# CH32H417MEU6-UHSIF-Top-R0.net
KiCad netlist of a schematic drawn in Altium Designer
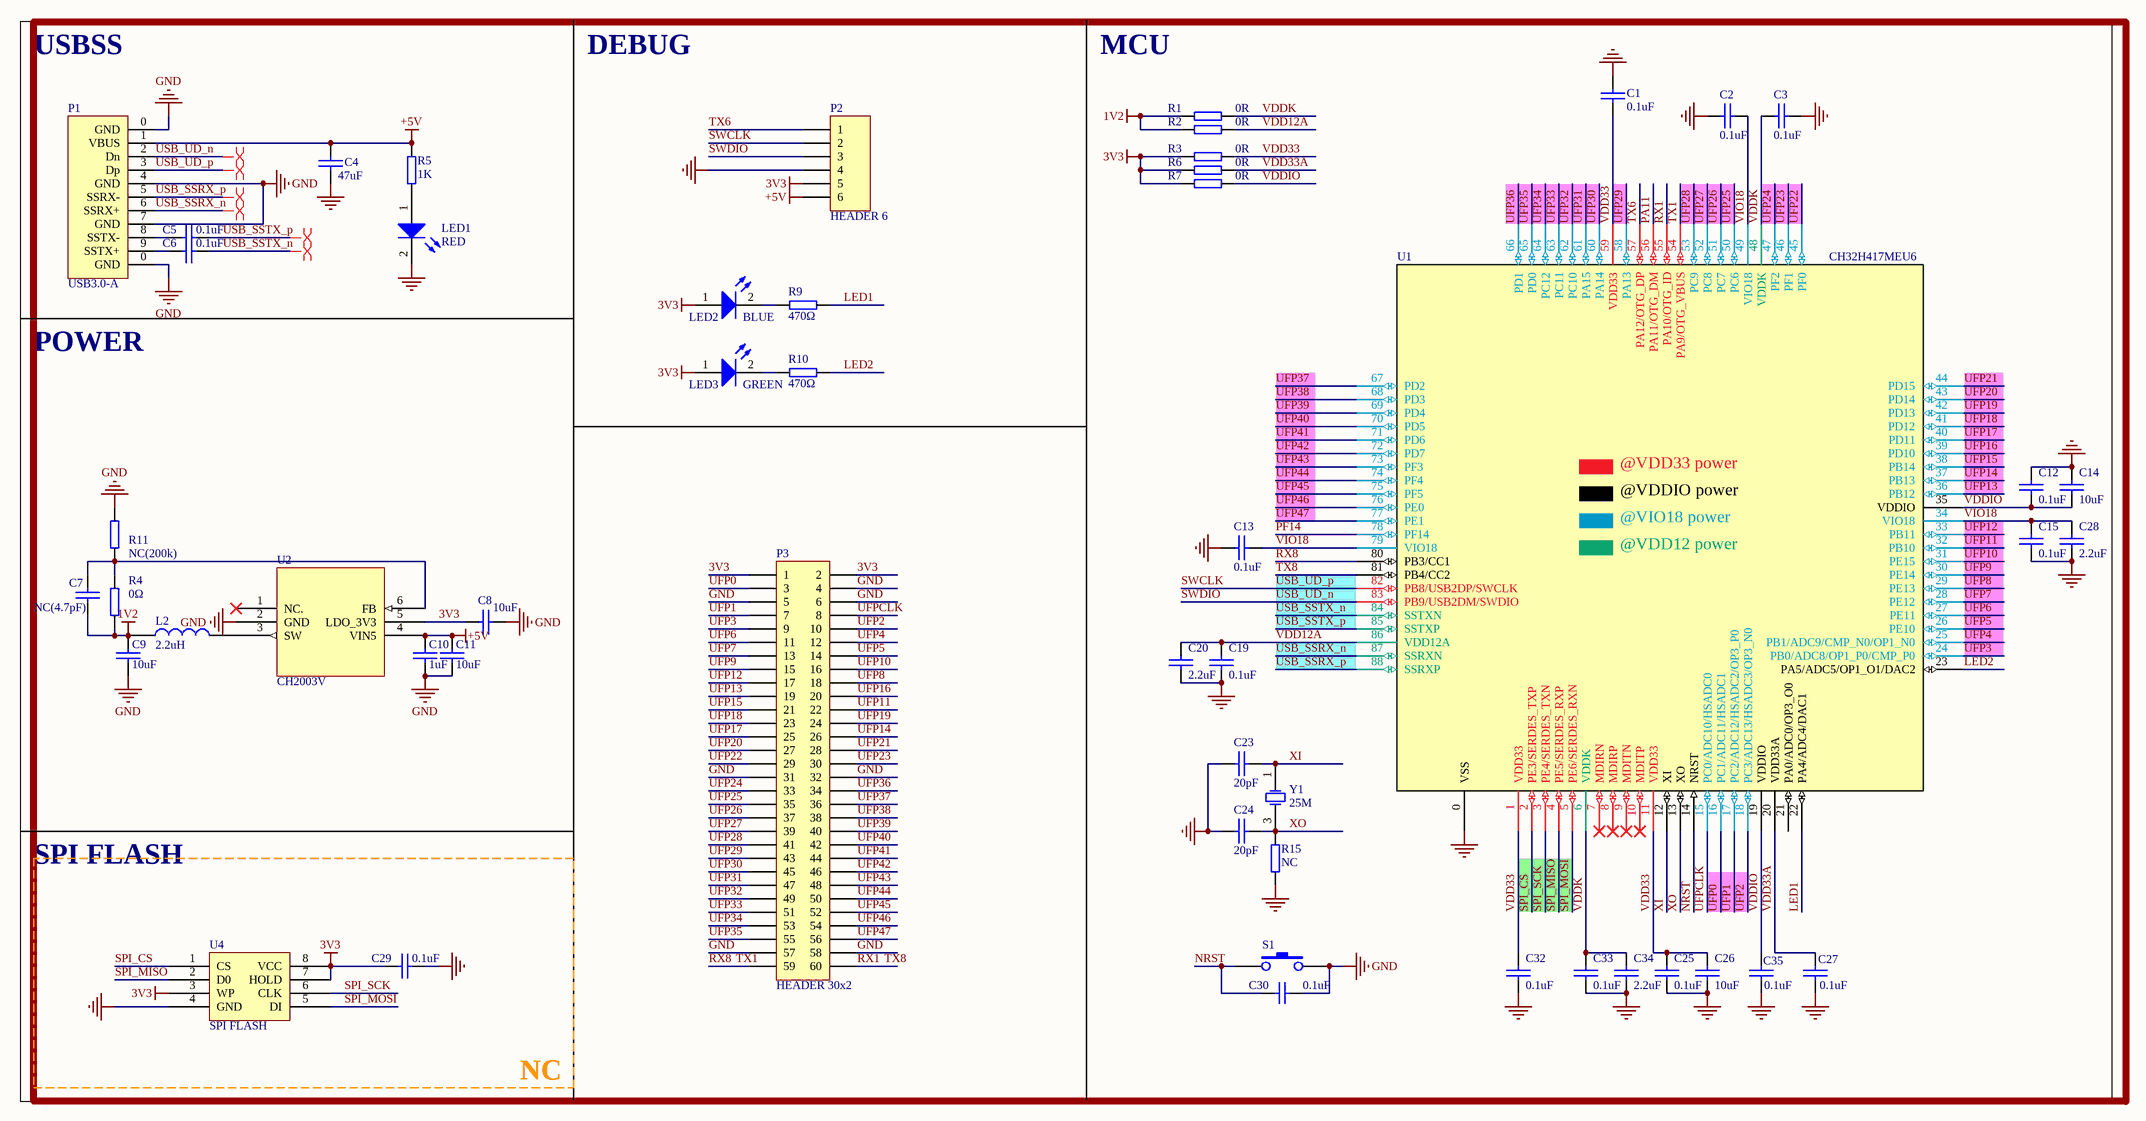
[diagram p0: CH32H417MEU6-UHSIF-Top-R0.SchDoc]

(export (version "E")
  (design (tool "Eeschema 10.0.6"))
  (components
    (comp (ref "C1")
      (value "0.1uF")
      (footprint "0402_C")
      (description "Capacitor")
      (libsource (lib "wch_sch_others") (part "CAP"))
    )
    (comp (ref "C2")
      (value "0.1uF")
      (footprint "0402_C")
      (description "Capacitor")
      (libsource (lib "wch_sch_others") (part "CAP"))
    )
    (comp (ref "C3")
      (value "0.1uF")
      (footprint "0402_C")
      (description "Capacitor")
      (libsource (lib "wch_sch_others") (part "CAP"))
    )
    (comp (ref "C4")
      (value "47uF")
      (footprint "3528_C")
      (description "Capacitor")
      (libsource (lib "wch_sch_others") (part "CAP"))
    )
    (comp (ref "C5")
      (value "0.1uF")
      (footprint "0402_C")
      (description "Capacitor")
      (libsource (lib "wch_sch_others") (part "CAP"))
    )
    (comp (ref "C6")
      (value "0.1uF")
      (footprint "0402_C")
      (description "Capacitor")
      (libsource (lib "wch_sch_others") (part "CAP"))
    )
    (comp (ref "C7")
      (value "NC(4.7pF)")
      (footprint "0402_C")
      (description "Capacitor")
      (libsource (lib "*") (part "CAP"))
    )
    (comp (ref "C8")
      (value "10uF")
      (footprint "0603_C")
      (description "Capacitor")
      (libsource (lib "") (part "CAP_1"))
    )
    (comp (ref "C9")
      (value "10uF")
      (footprint "0603_C")
      (description "Capacitor")
      (libsource (lib "") (part "CAP_1"))
    )
    (comp (ref "C10")
      (value "1uF")
      (footprint "0402_C")
      (description "Capacitor")
      (libsource (lib "*") (part "CAP"))
    )
    (comp (ref "C11")
      (value "10uF")
      (footprint "0603_C")
      (description "Capacitor")
      (libsource (lib "") (part "CAP_1"))
    )
    (comp (ref "C12")
      (value "0.1uF")
      (footprint "0402_C")
      (description "Capacitor")
      (libsource (lib "wch_sch_others") (part "CAP"))
    )
    (comp (ref "C13")
      (value "0.1uF")
      (footprint "0402_C")
      (description "Capacitor")
      (libsource (lib "wch_sch_others") (part "CAP"))
    )
    (comp (ref "C14")
      (value "10uF")
      (footprint "0402_C")
      (description "Capacitor")
      (libsource (lib "wch_sch_others") (part "CAP"))
    )
    (comp (ref "C15")
      (value "0.1uF")
      (footprint "0402_C")
      (description "Capacitor")
      (libsource (lib "wch_sch_others") (part "CAP"))
    )
    (comp (ref "C19")
      (value "0.1uF")
      (footprint "0402_C")
      (description "Capacitor")
      (libsource (lib "wch_sch_others") (part "CAP"))
    )
    (comp (ref "C20")
      (value "2.2uF")
      (footprint "0402_C")
      (description "Capacitor")
      (libsource (lib "wch_sch_others") (part "CAP"))
    )
    (comp (ref "C23")
      (value "20pF")
      (footprint "0402_C")
      (description "Capacitor")
      (libsource (lib "wch_sch_others") (part "CAP"))
    )
    (comp (ref "C24")
      (value "20pF")
      (footprint "0402_C")
      (description "Capacitor")
      (libsource (lib "wch_sch_others") (part "CAP"))
    )
    (comp (ref "C25")
      (value "0.1uF")
      (footprint "0402_C")
      (description "Capacitor")
      (libsource (lib "wch_sch_others") (part "CAP"))
    )
    (comp (ref "C26")
      (value "10uF")
      (footprint "0402_C")
      (description "Capacitor")
      (libsource (lib "wch_sch_others") (part "CAP"))
    )
    (comp (ref "C27")
      (value "0.1uF")
      (footprint "0402_C")
      (description "Capacitor")
      (libsource (lib "wch_sch_others") (part "CAP"))
    )
    (comp (ref "C28")
      (value "2.2uF")
      (footprint "0402_C")
      (description "Capacitor")
      (libsource (lib "wch_sch_others") (part "CAP"))
    )
    (comp (ref "C29")
      (value "0.1uF")
      (footprint "0402_C")
      (description "Capacitor")
      (libsource (lib "wch_sch_others") (part "CAP"))
    )
    (comp (ref "C30")
      (value "0.1uF")
      (footprint "0402_C")
      (description "Capacitor")
      (libsource (lib "Miscellaneous Devices") (part "Cap"))
    )
    (comp (ref "C32")
      (value "0.1uF")
      (footprint "0402_C")
      (description "Capacitor")
      (libsource (lib "wch_sch_others") (part "CAP"))
    )
    (comp (ref "C33")
      (value "0.1uF")
      (footprint "0402_C")
      (description "Capacitor")
      (libsource (lib "wch_sch_others") (part "CAP"))
    )
    (comp (ref "C34")
      (value "2.2uF")
      (footprint "0402_C")
      (description "Capacitor")
      (libsource (lib "wch_sch_others") (part "CAP"))
    )
    (comp (ref "C35")
      (value "0.1uF")
      (footprint "0402_C")
      (description "Capacitor")
      (libsource (lib "wch_sch_others") (part "CAP"))
    )
    (comp (ref "L2") (value "2.2uH") (footprint "CD32") (libsource (lib "*") (part "INDUCTOR")))
    (comp (ref "LED1")
      (value "RED")
      (footprint "MYPCB:0603+")
      (description "Typical INFRARED GaAs LED")
      (libsource (lib "wch_sch_others") (part "LED"))
    )
    (comp (ref "LED2")
      (value "BLUE")
      (footprint "MYPCB:0603+")
      (description "Typical INFRARED GaAs LED")
      (libsource (lib "wch_sch_others") (part "LED"))
    )
    (comp (ref "LED3")
      (value "GREEN")
      (footprint "MYPCB:0603+")
      (description "Typical INFRARED GaAs LED")
      (libsource (lib "wch_sch_others") (part "LED"))
    )
    (comp (ref "P1")
      (value "USB3.0-A")
      (footprint "USB3.0-A-Receptacle")
      (libsource (lib "wch_sch_others") (part "USB3.0-A"))
    )
    (comp (ref "P2")
      (value "HEADER 6")
      (footprint "SIP6-2.54mm")
      (description "Header, 6-Pin")
      (libsource (lib "wch_sch_others") (part "HEADER 6"))
    )
    (comp (ref "P3")
      (value "HEADER 30x2")
      (footprint "MYPCB:BTB-60P-P0.5-FR")
      (description "Header, 30-Pin, Dual row")
      (libsource (lib "wch_sch_others") (part "HEADER 30x2"))
    )
    (comp (ref "R1") (value "0R") (footprint "0603") (libsource (lib "wch_sch_others") (part "RES")))
    (comp (ref "R2") (value "0R") (footprint "0603") (libsource (lib "wch_sch_others") (part "RES")))
    (comp (ref "R3") (value "0R") (footprint "0603") (libsource (lib "wch_sch_others") (part "RES")))
    (comp (ref "R4") (value "0Ω") (footprint "0402") (libsource (lib "wch_sch_others") (part "RES")))
    (comp (ref "R5") (value "1K") (footprint "0402") (libsource (lib "wch_sch_others") (part "RES")))
    (comp (ref "R6") (value "0R") (footprint "0603") (libsource (lib "wch_sch_others") (part "RES")))
    (comp (ref "R7") (value "0R") (footprint "0603") (libsource (lib "wch_sch_others") (part "RES")))
    (comp (ref "R9") (value "470Ω") (footprint "0402") (libsource (lib "wch_sch_others") (part "RES")))
    (comp (ref "R10") (value "470Ω") (footprint "0402") (libsource (lib "wch_sch_others") (part "RES")))
    (comp (ref "R11") (value "NC(200k)") (footprint "0402") (libsource (lib "wch_sch_others") (part "RES")))
    (comp (ref "R15") (value "NC") (footprint "0402") (libsource (lib "*") (part "RES")))
    (comp (ref "S1") (value "~") (footprint "贴片按键") (libsource (lib "wch_sch_others") (part "KEY1")))
    (comp (ref "U1")
      (value "CH32H417MEU6")
      (footprint "QFN88_10X10")
      (description "RISC-V FPU HD-MCU, 384MHz, USB3.0 & PD, 100M Ethernet, DVP, SDMMC, QSPI, OPA, ADC, DAC")
      (libsource (lib "DHXXXSCH") (part "CH32H417MEU6"))
    )
    (comp (ref "U2")
      (value "CH2003V")
      (footprint "SOT-23-6")
      (description "Step-Down DC-DC Converter, 5V input, FB 0.6V, 800mA output, with LDO 3.3V * 200mA")
      (libsource (lib "DHXXXSCH") (part "CH2003K"))
    )
    (comp (ref "U4")
      (value "SPI FLASH")
      (footprint "SOIC-8_208mil")
      (libsource (lib "wch_sch_others") (part "W25Q64"))
    )
    (comp (ref "Y1")
      (value "25M")
      (footprint "XT3225")
      (description "Crystal Oscillator")
      (fields (field (name "PUBLISHER") "Altium Limited"))
      (libsource (lib "Miscellaneous Devices") (part "XTAL"))
    )
  )
  (nets
    (net (code "1") (name "+5V") (class "Default")
      (node (ref "C10") (pin "2") (pinfunction "2_2") (pintype "passive"))
      (node (ref "C11") (pin "2") (pinfunction "2_2") (pintype "passive"))
      (node (ref "C4") (pin "1") (pinfunction "1_1") (pintype "passive"))
      (node (ref "P1") (pin "1") (pinfunction "VBUS_1") (pintype "passive"))
      (node (ref "P2") (pin "6") (pinfunction "6_6") (pintype "passive"))
      (node (ref "R5") (pin "2") (pintype "passive"))
      (node (ref "U2") (pin "4") (pinfunction "VIN5_4") (pintype "power_in"))
    )
    (net (code "2") (name "/LED1") (class "Default")
      (node (ref "R9") (pin "1") (pintype "passive"))
      (node (ref "U1") (pin "22") (pinfunction "PA4/ADC4/DAC1_22") (pintype "bidirectional"))
    )
    (net (code "3") (name "/LED2") (class "Default")
      (node (ref "R10") (pin "1") (pintype "passive"))
      (node (ref "U1") (pin "23") (pinfunction "PA5/ADC5/OP1_O1/DAC2_23") (pintype "bidirectional"))
    )
    (net (code "4") (name "/NRST") (class "Default")
      (node (ref "C30") (pin "2") (pinfunction "2_2") (pintype "passive"))
      (node (ref "S1") (pin "1") (pinfunction "1_1") (pintype "passive"))
      (node (ref "U1") (pin "14") (pinfunction "NRST_14") (pintype "input"))
    )
    (net (code "5") (name "/PA11") (class "Default")
      (node (ref "U1") (pin "56") (pinfunction "PA11/OTG_DM_56") (pintype "bidirectional"))
    )
    (net (code "6") (name "/PF14") (class "Default")
      (node (ref "U1") (pin "78") (pinfunction "PF14_78") (pintype "bidirectional"))
    )
    (net (code "7") (name "/RX1") (class "Default")
      (node (ref "P3") (pin "60") (pinfunction "60_60") (pintype "passive"))
      (node (ref "U1") (pin "55") (pinfunction "PA10/OTG_ID_55") (pintype "bidirectional"))
      (node (ref "U1") (pin "81") (pinfunction "PB4/CC2_81") (pintype "bidirectional"))
    )
    (net (code "8") (name "/RX8") (class "Default")
      (node (ref "P3") (pin "59") (pinfunction "59_59") (pintype "passive"))
      (node (ref "U1") (pin "54") (pinfunction "PA9/OTG_VBUS_54") (pintype "bidirectional"))
      (node (ref "U1") (pin "80") (pinfunction "PB3/CC1_80") (pintype "bidirectional"))
    )
    (net (code "9") (name "/SPI_CS") (class "Default")
      (node (ref "U1") (pin "2") (pinfunction "PE3/SERDES_TXP_2") (pintype "bidirectional"))
      (node (ref "U4") (pin "1") (pinfunction "CS_1") (pintype "passive"))
    )
    (net (code "10") (name "/SPI_MISO") (class "Default")
      (node (ref "U1") (pin "4") (pinfunction "PE5/SERDES_RXP_4") (pintype "bidirectional"))
      (node (ref "U4") (pin "2") (pinfunction "D0_2") (pintype "passive"))
    )
    (net (code "11") (name "/SPI_MOSI") (class "Default")
      (node (ref "U1") (pin "5") (pinfunction "PE6/SERDES_RXN_5") (pintype "bidirectional"))
      (node (ref "U4") (pin "5") (pinfunction "DI_5") (pintype "passive"))
    )
    (net (code "12") (name "/SPI_SCK") (class "Default")
      (node (ref "U1") (pin "3") (pinfunction "PE4/SERDES_TXN_3") (pintype "bidirectional"))
      (node (ref "U4") (pin "6") (pinfunction "CLK_6") (pintype "passive"))
    )
    (net (code "13") (name "/SWCLK") (class "Default")
      (node (ref "P1") (pin "3") (pinfunction "Dp_3") (pintype "passive"))
      (node (ref "P2") (pin "2") (pinfunction "2_2") (pintype "passive"))
      (node (ref "U1") (pin "82") (pinfunction "PB8/USB2DP/SWCLK_82") (pintype "bidirectional"))
    )
    (net (code "14") (name "/SWDIO") (class "Default")
      (node (ref "P1") (pin "2") (pinfunction "Dn_2") (pintype "passive"))
      (node (ref "P2") (pin "3") (pinfunction "3_3") (pintype "passive"))
      (node (ref "U1") (pin "83") (pinfunction "PB9/USB2DM/SWDIO_83") (pintype "bidirectional"))
    )
    (net (code "15") (name "/TX6") (class "Default")
      (node (ref "P2") (pin "1") (pinfunction "1_1") (pintype "passive"))
      (node (ref "U1") (pin "57") (pinfunction "PA12/OTG_DP_57") (pintype "bidirectional"))
    )
    (net (code "16") (name "/UFP0") (class "Default")
      (node (ref "P3") (pin "3") (pinfunction "3_3") (pintype "passive"))
      (node (ref "U1") (pin "16") (pinfunction "PC1/ADC11/HSADC1_16") (pintype "bidirectional"))
    )
    (net (code "17") (name "/UFP1") (class "Default")
      (node (ref "P3") (pin "7") (pinfunction "7_7") (pintype "passive"))
      (node (ref "U1") (pin "17") (pinfunction "PC2/ADC12/HSADC2/OP3_P0_17") (pintype "bidirectional"))
    )
    (net (code "18") (name "/UFP2") (class "Default")
      (node (ref "P3") (pin "10") (pinfunction "10_10") (pintype "passive"))
      (node (ref "U1") (pin "18") (pinfunction "PC3/ADC13/HSADC3/OP3_N0_18") (pintype "bidirectional"))
    )
    (net (code "19") (name "/UFP3") (class "Default")
      (node (ref "P3") (pin "9") (pinfunction "9_9") (pintype "passive"))
      (node (ref "U1") (pin "24") (pinfunction "PB0/ADC8/OP1_P0/CMP_P0_24") (pintype "bidirectional"))
    )
    (net (code "20") (name "/UFP4") (class "Default")
      (node (ref "P3") (pin "12") (pinfunction "12_12") (pintype "passive"))
      (node (ref "U1") (pin "25") (pinfunction "PB1/ADC9/CMP_N0/OP1_N0_25") (pintype "bidirectional"))
    )
    (net (code "21") (name "/UFP5") (class "Default")
      (node (ref "P3") (pin "14") (pinfunction "14_14") (pintype "passive"))
      (node (ref "U1") (pin "26") (pinfunction "PE10_26") (pintype "bidirectional"))
    )
    (net (code "22") (name "/UFP6") (class "Default")
      (node (ref "P3") (pin "11") (pinfunction "11_11") (pintype "passive"))
      (node (ref "U1") (pin "27") (pinfunction "PE11_27") (pintype "bidirectional"))
    )
    (net (code "23") (name "/UFP7") (class "Default")
      (node (ref "P3") (pin "13") (pinfunction "13_13") (pintype "passive"))
      (node (ref "U1") (pin "28") (pinfunction "PE12_28") (pintype "bidirectional"))
    )
    (net (code "24") (name "/UFP8") (class "Default")
      (node (ref "P3") (pin "18") (pinfunction "18_18") (pintype "passive"))
      (node (ref "U1") (pin "29") (pinfunction "PE13_29") (pintype "bidirectional"))
    )
    (net (code "25") (name "/UFP9") (class "Default")
      (node (ref "P3") (pin "15") (pinfunction "15_15") (pintype "passive"))
      (node (ref "U1") (pin "30") (pinfunction "PE14_30") (pintype "bidirectional"))
    )
    (net (code "26") (name "/UFP10") (class "Default")
      (node (ref "P3") (pin "16") (pinfunction "16_16") (pintype "passive"))
      (node (ref "U1") (pin "31") (pinfunction "PE15_31") (pintype "bidirectional"))
    )
    (net (code "27") (name "/UFP11") (class "Default")
      (node (ref "P3") (pin "22") (pinfunction "22_22") (pintype "passive"))
      (node (ref "U1") (pin "32") (pinfunction "PB10_32") (pintype "bidirectional"))
    )
    (net (code "28") (name "/UFP12") (class "Default")
      (node (ref "P3") (pin "17") (pinfunction "17_17") (pintype "passive"))
      (node (ref "U1") (pin "33") (pinfunction "PB11_33") (pintype "bidirectional"))
    )
    (net (code "29") (name "/UFP13") (class "Default")
      (node (ref "P3") (pin "19") (pinfunction "19_19") (pintype "passive"))
      (node (ref "U1") (pin "36") (pinfunction "PB12_36") (pintype "bidirectional"))
    )
    (net (code "30") (name "/UFP14") (class "Default")
      (node (ref "P3") (pin "26") (pinfunction "26_26") (pintype "passive"))
      (node (ref "U1") (pin "37") (pinfunction "PB13_37") (pintype "bidirectional"))
    )
    (net (code "31") (name "/UFP15") (class "Default")
      (node (ref "P3") (pin "21") (pinfunction "21_21") (pintype "passive"))
      (node (ref "U1") (pin "38") (pinfunction "PB14_38") (pintype "bidirectional"))
    )
    (net (code "32") (name "/UFP16") (class "Default")
      (node (ref "P3") (pin "20") (pinfunction "20_20") (pintype "passive"))
      (node (ref "U1") (pin "39") (pinfunction "PD10_39") (pintype "bidirectional"))
    )
    (net (code "33") (name "/UFP17") (class "Default")
      (node (ref "P3") (pin "25") (pinfunction "25_25") (pintype "passive"))
      (node (ref "U1") (pin "40") (pinfunction "PD11_40") (pintype "bidirectional"))
    )
    (net (code "34") (name "/UFP18") (class "Default")
      (node (ref "P3") (pin "23") (pinfunction "23_23") (pintype "passive"))
      (node (ref "U1") (pin "41") (pinfunction "PD12_41") (pintype "bidirectional"))
    )
    (net (code "35") (name "/UFP19") (class "Default")
      (node (ref "P3") (pin "24") (pinfunction "24_24") (pintype "passive"))
      (node (ref "U1") (pin "42") (pinfunction "PD13_42") (pintype "bidirectional"))
    )
    (net (code "36") (name "/UFP20") (class "Default")
      (node (ref "P3") (pin "27") (pinfunction "27_27") (pintype "passive"))
      (node (ref "U1") (pin "43") (pinfunction "PD14_43") (pintype "bidirectional"))
    )
    (net (code "37") (name "/UFP21") (class "Default")
      (node (ref "P3") (pin "28") (pinfunction "28_28") (pintype "passive"))
      (node (ref "U1") (pin "44") (pinfunction "PD15_44") (pintype "bidirectional"))
    )
    (net (code "38") (name "/UFP22") (class "Default")
      (node (ref "P3") (pin "29") (pinfunction "29_29") (pintype "passive"))
      (node (ref "U1") (pin "45") (pinfunction "PF0_45") (pintype "bidirectional"))
    )
    (net (code "39") (name "/UFP23") (class "Default")
      (node (ref "P3") (pin "30") (pinfunction "30_30") (pintype "passive"))
      (node (ref "U1") (pin "46") (pinfunction "PF1_46") (pintype "bidirectional"))
    )
    (net (code "40") (name "/UFP24") (class "Default")
      (node (ref "P3") (pin "33") (pinfunction "33_33") (pintype "passive"))
      (node (ref "U1") (pin "47") (pinfunction "PF2_47") (pintype "bidirectional"))
    )
    (net (code "41") (name "/UFP25") (class "Default")
      (node (ref "P3") (pin "35") (pinfunction "35_35") (pintype "passive"))
      (node (ref "U1") (pin "50") (pinfunction "PC6_50") (pintype "bidirectional"))
    )
    (net (code "42") (name "/UFP26") (class "Default")
      (node (ref "P3") (pin "37") (pinfunction "37_37") (pintype "passive"))
      (node (ref "U1") (pin "51") (pinfunction "PC7_51") (pintype "bidirectional"))
    )
    (net (code "43") (name "/UFP27") (class "Default")
      (node (ref "P3") (pin "39") (pinfunction "39_39") (pintype "passive"))
      (node (ref "U1") (pin "52") (pinfunction "PC8_52") (pintype "bidirectional"))
    )
    (net (code "44") (name "/UFP28") (class "Default")
      (node (ref "P3") (pin "41") (pinfunction "41_41") (pintype "passive"))
      (node (ref "U1") (pin "53") (pinfunction "PC9_53") (pintype "bidirectional"))
    )
    (net (code "45") (name "/UFP29") (class "Default")
      (node (ref "P3") (pin "43") (pinfunction "43_43") (pintype "passive"))
      (node (ref "U1") (pin "58") (pinfunction "PA13_58") (pintype "bidirectional"))
    )
    (net (code "46") (name "/UFP30") (class "Default")
      (node (ref "P3") (pin "45") (pinfunction "45_45") (pintype "passive"))
      (node (ref "U1") (pin "60") (pinfunction "PA14_60") (pintype "bidirectional"))
    )
    (net (code "47") (name "/UFP31") (class "Default")
      (node (ref "P3") (pin "47") (pinfunction "47_47") (pintype "passive"))
      (node (ref "U1") (pin "61") (pinfunction "PA15_61") (pintype "bidirectional"))
    )
    (net (code "48") (name "/UFP32") (class "Default")
      (node (ref "P3") (pin "49") (pinfunction "49_49") (pintype "passive"))
      (node (ref "U1") (pin "62") (pinfunction "PC10_62") (pintype "bidirectional"))
    )
    (net (code "49") (name "/UFP33") (class "Default")
      (node (ref "P3") (pin "51") (pinfunction "51_51") (pintype "passive"))
      (node (ref "U1") (pin "63") (pinfunction "PC11_63") (pintype "bidirectional"))
    )
    (net (code "50") (name "/UFP34") (class "Default")
      (node (ref "P3") (pin "53") (pinfunction "53_53") (pintype "passive"))
      (node (ref "U1") (pin "64") (pinfunction "PC12_64") (pintype "bidirectional"))
    )
    (net (code "51") (name "/UFP35") (class "Default")
      (node (ref "P3") (pin "55") (pinfunction "55_55") (pintype "passive"))
      (node (ref "U1") (pin "65") (pinfunction "PD0_65") (pintype "bidirectional"))
    )
    (net (code "52") (name "/UFP36") (class "Default")
      (node (ref "P3") (pin "34") (pinfunction "34_34") (pintype "passive"))
      (node (ref "U1") (pin "66") (pinfunction "PD1_66") (pintype "bidirectional"))
    )
    (net (code "53") (name "/UFP37") (class "Default")
      (node (ref "P3") (pin "36") (pinfunction "36_36") (pintype "passive"))
      (node (ref "U1") (pin "67") (pinfunction "PD2_67") (pintype "bidirectional"))
    )
    (net (code "54") (name "/UFP38") (class "Default")
      (node (ref "P3") (pin "38") (pinfunction "38_38") (pintype "passive"))
      (node (ref "U1") (pin "68") (pinfunction "PD3_68") (pintype "bidirectional"))
    )
    (net (code "55") (name "/UFP39") (class "Default")
      (node (ref "P3") (pin "40") (pinfunction "40_40") (pintype "passive"))
      (node (ref "U1") (pin "69") (pinfunction "PD4_69") (pintype "bidirectional"))
    )
    (net (code "56") (name "/UFP40") (class "Default")
      (node (ref "P3") (pin "42") (pinfunction "42_42") (pintype "passive"))
      (node (ref "U1") (pin "70") (pinfunction "PD5_70") (pintype "bidirectional"))
    )
    (net (code "57") (name "/UFP41") (class "Default")
      (node (ref "P3") (pin "44") (pinfunction "44_44") (pintype "passive"))
      (node (ref "U1") (pin "71") (pinfunction "PD6_71") (pintype "bidirectional"))
    )
    (net (code "58") (name "/UFP42") (class "Default")
      (node (ref "P3") (pin "46") (pinfunction "46_46") (pintype "passive"))
      (node (ref "U1") (pin "72") (pinfunction "PD7_72") (pintype "bidirectional"))
    )
    (net (code "59") (name "/UFP43") (class "Default")
      (node (ref "P3") (pin "48") (pinfunction "48_48") (pintype "passive"))
      (node (ref "U1") (pin "73") (pinfunction "PF3_73") (pintype "bidirectional"))
    )
    (net (code "60") (name "/UFP44") (class "Default")
      (node (ref "P3") (pin "50") (pinfunction "50_50") (pintype "passive"))
      (node (ref "U1") (pin "74") (pinfunction "PF4_74") (pintype "bidirectional"))
    )
    (net (code "61") (name "/UFP45") (class "Default")
      (node (ref "P3") (pin "52") (pinfunction "52_52") (pintype "passive"))
      (node (ref "U1") (pin "75") (pinfunction "PF5_75") (pintype "bidirectional"))
    )
    (net (code "62") (name "/UFP46") (class "Default")
      (node (ref "P3") (pin "54") (pinfunction "54_54") (pintype "passive"))
      (node (ref "U1") (pin "76") (pinfunction "PE0_76") (pintype "bidirectional"))
    )
    (net (code "63") (name "/UFP47") (class "Default")
      (node (ref "P3") (pin "56") (pinfunction "56_56") (pintype "passive"))
      (node (ref "U1") (pin "77") (pinfunction "PE1_77") (pintype "bidirectional"))
    )
    (net (code "64") (name "/UFPCLK") (class "Default")
      (node (ref "P3") (pin "8") (pinfunction "8_8") (pintype "passive"))
      (node (ref "U1") (pin "15") (pinfunction "PC0/ADC10/HSADC0_15") (pintype "bidirectional"))
    )
    (net (code "65") (name "/USB_SSRX_n") (class "Default")
      (node (ref "P1") (pin "6") (pinfunction "SSRX+_6") (pintype "passive"))
      (node (ref "U1") (pin "87") (pinfunction "SSRXN_87") (pintype "bidirectional"))
    )
    (net (code "66") (name "/USB_SSRX_p") (class "Default")
      (node (ref "P1") (pin "5") (pinfunction "SSRX-_5") (pintype "passive"))
      (node (ref "U1") (pin "88") (pinfunction "SSRXP_88") (pintype "bidirectional"))
    )
    (net (code "67") (name "/USB_SSTX_n") (class "Default")
      (node (ref "C6") (pin "1") (pinfunction "1_1") (pintype "passive"))
      (node (ref "U1") (pin "84") (pinfunction "SSTXN_84") (pintype "bidirectional"))
    )
    (net (code "68") (name "/USB_SSTX_p") (class "Default")
      (node (ref "C5") (pin "1") (pinfunction "1_1") (pintype "passive"))
      (node (ref "U1") (pin "85") (pinfunction "SSTXP_85") (pintype "bidirectional"))
    )
    (net (code "69") (name "/VDD12A") (class "Default")
      (node (ref "C19") (pin "2") (pinfunction "2_2") (pintype "passive"))
      (node (ref "C20") (pin "2") (pinfunction "2_2") (pintype "passive"))
      (node (ref "R2") (pin "1") (pintype "passive"))
      (node (ref "U1") (pin "86") (pinfunction "VDD12A_86") (pintype "power_in"))
    )
    (net (code "70") (name "/VDD33") (class "Default")
      (node (ref "C1") (pin "1") (pinfunction "1_1") (pintype "passive"))
      (node (ref "C25") (pin "2") (pinfunction "2_2") (pintype "passive"))
      (node (ref "C26") (pin "2") (pinfunction "2_2") (pintype "passive"))
      (node (ref "C32") (pin "2") (pinfunction "2_2") (pintype "passive"))
      (node (ref "R3") (pin "1") (pintype "passive"))
      (node (ref "U1") (pin "1") (pinfunction "VDD33_1") (pintype "power_in"))
      (node (ref "U1") (pin "11") (pinfunction "VDD33_11") (pintype "power_in"))
      (node (ref "U1") (pin "59") (pinfunction "VDD33_59") (pintype "power_in"))
    )
    (net (code "71") (name "/VDD33A") (class "Default")
      (node (ref "C27") (pin "2") (pinfunction "2_2") (pintype "passive"))
      (node (ref "R6") (pin "1") (pintype "passive"))
      (node (ref "U1") (pin "20") (pinfunction "VDD33A_20") (pintype "power_in"))
    )
    (net (code "72") (name "/VDDIO") (class "Default")
      (node (ref "C12") (pin "1") (pinfunction "1_1") (pintype "passive"))
      (node (ref "C14") (pin "1") (pinfunction "1_1") (pintype "passive"))
      (node (ref "C35") (pin "2") (pinfunction "2_2") (pintype "passive"))
      (node (ref "R7") (pin "1") (pintype "passive"))
      (node (ref "U1") (pin "19") (pinfunction "VDDIO_19") (pintype "power_in"))
      (node (ref "U1") (pin "35") (pinfunction "VDDIO_35") (pintype "power_in"))
    )
    (net (code "73") (name "/VDDK") (class "Default")
      (node (ref "C3") (pin "2") (pinfunction "2_2") (pintype "passive"))
      (node (ref "C33") (pin "2") (pinfunction "2_2") (pintype "passive"))
      (node (ref "C34") (pin "2") (pinfunction "2_2") (pintype "passive"))
      (node (ref "R1") (pin "1") (pintype "passive"))
      (node (ref "U1") (pin "48") (pinfunction "VDDK_48") (pintype "power_in"))
      (node (ref "U1") (pin "6") (pinfunction "VDDK_6") (pintype "power_in"))
    )
    (net (code "74") (name "/VIO18") (class "Default")
      (node (ref "C13") (pin "1") (pinfunction "1_1") (pintype "passive"))
      (node (ref "C15") (pin "2") (pinfunction "2_2") (pintype "passive"))
      (node (ref "C2") (pin "1") (pinfunction "1_1") (pintype "passive"))
      (node (ref "C28") (pin "2") (pinfunction "2_2") (pintype "passive"))
      (node (ref "U1") (pin "34") (pinfunction "VIO18_34") (pintype "power_in"))
      (node (ref "U1") (pin "49") (pinfunction "VIO18_49") (pintype "power_in"))
      (node (ref "U1") (pin "79") (pinfunction "VIO18_79") (pintype "power_in"))
    )
    (net (code "75") (name "/XI") (class "Default")
      (node (ref "C23") (pin "2") (pinfunction "2_2") (pintype "passive"))
      (node (ref "U1") (pin "12") (pinfunction "XI_12") (pintype "bidirectional"))
      (node (ref "Y1") (pin "1") (pinfunction "OSC1_1") (pintype "passive"))
    )
    (net (code "76") (name "/XO") (class "Default")
      (node (ref "C24") (pin "2") (pinfunction "2_2") (pintype "passive"))
      (node (ref "R15") (pin "2") (pintype "passive"))
      (node (ref "U1") (pin "13") (pinfunction "XO_13") (pintype "bidirectional"))
      (node (ref "Y1") (pin "3") (pinfunction "OSC2_3") (pintype "passive"))
    )
    (net (code "77") (name "1V2") (class "Default")
      (node (ref "C7") (pin "1") (pinfunction "1_1") (pintype "passive"))
      (node (ref "C9") (pin "2") (pinfunction "2_2") (pintype "passive"))
      (node (ref "L2") (pin "2") (pinfunction "2_2") (pintype "passive"))
      (node (ref "R1") (pin "2") (pintype "passive"))
      (node (ref "R2") (pin "2") (pintype "passive"))
      (node (ref "R4") (pin "1") (pintype "passive"))
    )
    (net (code "78") (name "3V3") (class "Default")
      (node (ref "C29") (pin "2") (pinfunction "2_2") (pintype "passive"))
      (node (ref "C8") (pin "2") (pinfunction "2_2") (pintype "passive"))
      (node (ref "LED2") (pin "1") (pinfunction "A_1") (pintype "passive"))
      (node (ref "LED3") (pin "1") (pinfunction "A_1") (pintype "passive"))
      (node (ref "P2") (pin "5") (pinfunction "5_5") (pintype "passive"))
      (node (ref "P3") (pin "1") (pinfunction "1_1") (pintype "passive"))
      (node (ref "P3") (pin "2") (pinfunction "2_2") (pintype "passive"))
      (node (ref "R3") (pin "2") (pintype "passive"))
      (node (ref "R6") (pin "2") (pintype "passive"))
      (node (ref "R7") (pin "2") (pintype "passive"))
      (node (ref "U2") (pin "5") (pinfunction "LDO_3V3_5") (pintype "power_in"))
      (node (ref "U4") (pin "3") (pinfunction "WP_3") (pintype "passive"))
      (node (ref "U4") (pin "7") (pinfunction "HOLD_7") (pintype "passive"))
      (node (ref "U4") (pin "8") (pinfunction "VCC_8") (pintype "passive"))
    )
    (net (code "79") (name "GND") (class "Default")
      (node (ref "C1") (pin "2") (pinfunction "2_2") (pintype "passive"))
      (node (ref "C10") (pin "1") (pinfunction "1_1") (pintype "passive"))
      (node (ref "C11") (pin "1") (pinfunction "1_1") (pintype "passive"))
      (node (ref "C12") (pin "2") (pinfunction "2_2") (pintype "passive"))
      (node (ref "C13") (pin "2") (pinfunction "2_2") (pintype "passive"))
      (node (ref "C14") (pin "2") (pinfunction "2_2") (pintype "passive"))
      (node (ref "C15") (pin "1") (pinfunction "1_1") (pintype "passive"))
      (node (ref "C19") (pin "1") (pinfunction "1_1") (pintype "passive"))
      (node (ref "C2") (pin "2") (pinfunction "2_2") (pintype "passive"))
      (node (ref "C20") (pin "1") (pinfunction "1_1") (pintype "passive"))
      (node (ref "C23") (pin "1") (pinfunction "1_1") (pintype "passive"))
      (node (ref "C24") (pin "1") (pinfunction "1_1") (pintype "passive"))
      (node (ref "C25") (pin "1") (pinfunction "1_1") (pintype "passive"))
      (node (ref "C26") (pin "1") (pinfunction "1_1") (pintype "passive"))
      (node (ref "C27") (pin "1") (pinfunction "1_1") (pintype "passive"))
      (node (ref "C28") (pin "1") (pinfunction "1_1") (pintype "passive"))
      (node (ref "C29") (pin "1") (pinfunction "1_1") (pintype "passive"))
      (node (ref "C3") (pin "1") (pinfunction "1_1") (pintype "passive"))
      (node (ref "C30") (pin "1") (pinfunction "1_1") (pintype "passive"))
      (node (ref "C32") (pin "1") (pinfunction "1_1") (pintype "passive"))
      (node (ref "C33") (pin "1") (pinfunction "1_1") (pintype "passive"))
      (node (ref "C34") (pin "1") (pinfunction "1_1") (pintype "passive"))
      (node (ref "C35") (pin "1") (pinfunction "1_1") (pintype "passive"))
      (node (ref "C4") (pin "2") (pinfunction "2_2") (pintype "passive"))
      (node (ref "C8") (pin "1") (pinfunction "1_1") (pintype "passive"))
      (node (ref "C9") (pin "1") (pinfunction "1_1") (pintype "passive"))
      (node (ref "LED1") (pin "2") (pinfunction "K_2") (pintype "passive"))
      (node (ref "P1") (pin "0") (pinfunction "GND_0") (pintype "passive"))
      (node (ref "P1") (pin "4") (pinfunction "GND_4") (pintype "passive"))
      (node (ref "P1") (pin "7") (pinfunction "GND_7") (pintype "passive"))
      (node (ref "P2") (pin "4") (pinfunction "4_4") (pintype "passive"))
      (node (ref "P3") (pin "31") (pinfunction "31_31") (pintype "passive"))
      (node (ref "P3") (pin "32") (pinfunction "32_32") (pintype "passive"))
      (node (ref "P3") (pin "4") (pinfunction "4_4") (pintype "passive"))
      (node (ref "P3") (pin "5") (pinfunction "5_5") (pintype "passive"))
      (node (ref "P3") (pin "57") (pinfunction "57_57") (pintype "passive"))
      (node (ref "P3") (pin "58") (pinfunction "58_58") (pintype "passive"))
      (node (ref "P3") (pin "6") (pinfunction "6_6") (pintype "passive"))
      (node (ref "R11") (pin "2") (pintype "passive"))
      (node (ref "R15") (pin "1") (pintype "passive"))
      (node (ref "S1") (pin "2") (pinfunction "2_2") (pintype "passive"))
      (node (ref "U1") (pin "0") (pinfunction "VSS_0") (pintype "power_in"))
      (node (ref "U2") (pin "2") (pinfunction "GND_2") (pintype "power_in"))
      (node (ref "U4") (pin "4") (pinfunction "GND_4") (pintype "passive"))
    )
    (net (code "80") (name "Net-(LED1-A)") (class "Default")
      (node (ref "LED1") (pin "1") (pinfunction "A_1") (pintype "passive"))
      (node (ref "R5") (pin "1") (pintype "passive"))
    )
    (net (code "81") (name "Net-(LED2-K)") (class "Default")
      (node (ref "LED2") (pin "2") (pinfunction "K_2") (pintype "passive"))
      (node (ref "R9") (pin "2") (pintype "passive"))
    )
    (net (code "82") (name "Net-(LED3-K)") (class "Default")
      (node (ref "LED3") (pin "2") (pinfunction "K_2") (pintype "passive"))
      (node (ref "R10") (pin "2") (pintype "passive"))
    )
    (net (code "83") (name "Net-(P1-SSTX+)") (class "Default")
      (node (ref "C6") (pin "2") (pinfunction "2_2") (pintype "passive"))
      (node (ref "P1") (pin "9") (pinfunction "SSTX+_9") (pintype "passive"))
    )
    (net (code "84") (name "Net-(P1-SSTX-)") (class "Default")
      (node (ref "C5") (pin "2") (pinfunction "2_2") (pintype "passive"))
      (node (ref "P1") (pin "8") (pinfunction "SSTX-_8") (pintype "passive"))
    )
    (net (code "85") (name "Net-(U2-FB)") (class "Default")
      (node (ref "C7") (pin "2") (pinfunction "2_2") (pintype "passive"))
      (node (ref "R11") (pin "1") (pintype "passive"))
      (node (ref "R4") (pin "2") (pintype "passive"))
      (node (ref "U2") (pin "6") (pinfunction "FB_6") (pintype "input"))
    )
    (net (code "86") (name "Net-(U2-SW)") (class "Default")
      (node (ref "L2") (pin "1") (pinfunction "1_1") (pintype "passive"))
      (node (ref "U2") (pin "3") (pinfunction "SW_3") (pintype "output"))
    )
    (net (code "87") (name "unconnected-(U1-MDIRN-Pad7)") (class "Default")
      (node (ref "U1") (pin "7") (pinfunction "MDIRN_7") (pintype "bidirectional+no_connect"))
    )
    (net (code "88") (name "unconnected-(U1-MDIRP-Pad8)") (class "Default")
      (node (ref "U1") (pin "8") (pinfunction "MDIRP_8") (pintype "bidirectional+no_connect"))
    )
    (net (code "89") (name "unconnected-(U1-MDITN-Pad9)") (class "Default")
      (node (ref "U1") (pin "9") (pinfunction "MDITN_9") (pintype "bidirectional+no_connect"))
    )
    (net (code "90") (name "unconnected-(U1-MDITP-Pad10)") (class "Default")
      (node (ref "U1") (pin "10") (pinfunction "MDITP_10") (pintype "bidirectional+no_connect"))
    )
    (net (code "91") (name "unconnected-(U1-PA0{slash}ADC0{slash}OP3_O0-Pad21)") (class "Default")
      (node (ref "U1") (pin "21") (pinfunction "PA0/ADC0/OP3_O0_21") (pintype "bidirectional"))
    )
    (net (code "92") (name "unconnected-(U2-NC.-Pad1)") (class "Default")
      (node (ref "U2") (pin "1") (pinfunction "NC._1") (pintype "passive+no_connect"))
    )
  )
)
